# STM32.net
KiCad netlist of a schematic drawn in Altium Designer
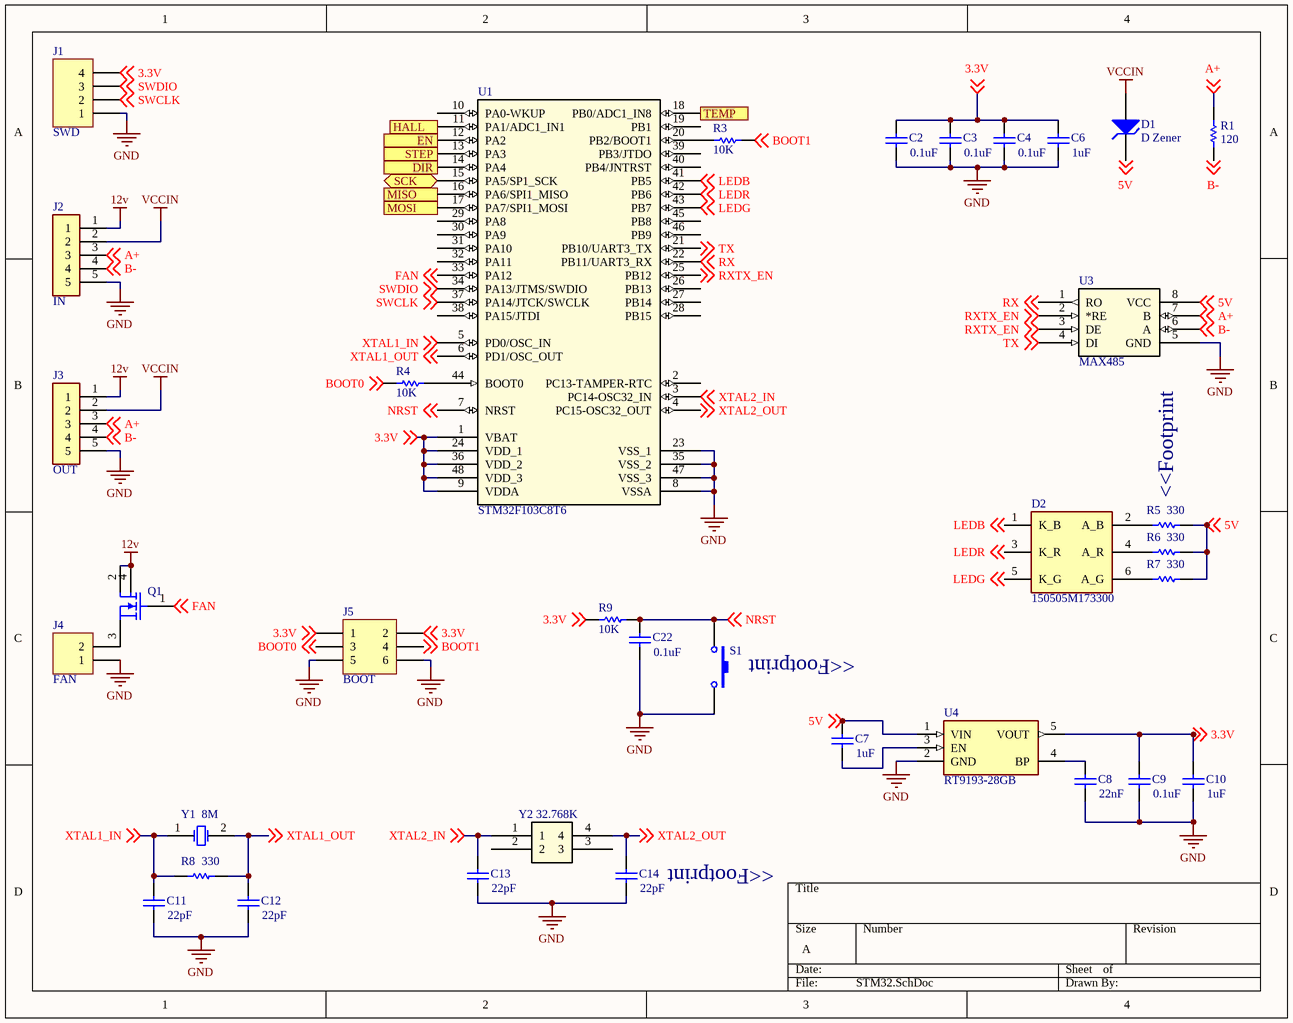
[diagram p0: STM32.SchDoc]

(export (version "E")
  (design (tool "Eeschema 10.0.6"))
  (components
    (comp (ref "C2")
      (value "0.1uF")
      (footprint "RAD-0.3")
      (description "Capacitor")
      (fields (field (name "PUBLISHER") "Altium Limited"))
      (libsource (lib "Miscellaneous Devices") (part "Cap"))
    )
    (comp (ref "C3")
      (value "0.1uF")
      (footprint "RAD-0.3")
      (description "Capacitor")
      (fields (field (name "PUBLISHER") "Altium Limited"))
      (libsource (lib "Miscellaneous Devices") (part "Cap"))
    )
    (comp (ref "C4")
      (value "0.1uF")
      (footprint "RAD-0.3")
      (description "Capacitor")
      (fields (field (name "PUBLISHER") "Altium Limited"))
      (libsource (lib "Miscellaneous Devices") (part "Cap"))
    )
    (comp (ref "C6")
      (value "1uF")
      (footprint "RAD-0.3")
      (description "Capacitor")
      (fields (field (name "PUBLISHER") "Altium Limited"))
      (libsource (lib "Miscellaneous Devices") (part "Cap"))
    )
    (comp (ref "C7")
      (value "1uF")
      (footprint "RAD-0.3")
      (description "Capacitor")
      (fields (field (name "PUBLISHER") "Altium Limited"))
      (libsource (lib "Miscellaneous Devices") (part "Cap"))
    )
    (comp (ref "C8")
      (value "22nF")
      (footprint "RAD-0.3")
      (description "Capacitor")
      (fields (field (name "PUBLISHER") "Altium Limited"))
      (libsource (lib "Miscellaneous Devices") (part "Cap"))
    )
    (comp (ref "C9")
      (value "0.1uF")
      (footprint "RAD-0.3")
      (description "Capacitor")
      (fields (field (name "PUBLISHER") "Altium Limited"))
      (libsource (lib "Miscellaneous Devices") (part "Cap"))
    )
    (comp (ref "C10")
      (value "1uF")
      (footprint "RAD-0.3")
      (description "Capacitor")
      (fields (field (name "PUBLISHER") "Altium Limited"))
      (libsource (lib "Miscellaneous Devices") (part "Cap"))
    )
    (comp (ref "C11")
      (value "22pF")
      (footprint "RAD-0.3")
      (description "Capacitor")
      (fields (field (name "PUBLISHER") "Altium Limited"))
      (libsource (lib "Miscellaneous Devices") (part "Cap"))
    )
    (comp (ref "C12")
      (value "22pF")
      (footprint "RAD-0.3")
      (description "Capacitor")
      (fields (field (name "PUBLISHER") "Altium Limited"))
      (libsource (lib "Miscellaneous Devices") (part "Cap"))
    )
    (comp (ref "C13")
      (value "22pF")
      (footprint "RAD-0.3")
      (description "Capacitor")
      (fields (field (name "PUBLISHER") "Altium Limited"))
      (libsource (lib "Miscellaneous Devices") (part "Cap"))
    )
    (comp (ref "C14")
      (value "22pF")
      (footprint "RAD-0.3")
      (description "Capacitor")
      (fields (field (name "PUBLISHER") "Altium Limited"))
      (libsource (lib "Miscellaneous Devices") (part "Cap"))
    )
    (comp (ref "C22")
      (value "0.1uF")
      (footprint "RAD-0.3")
      (description "Capacitor")
      (fields (field (name "PUBLISHER") "Altium Limited"))
      (libsource (lib "Miscellaneous Devices") (part "Cap"))
    )
    (comp (ref "D1")
      (value "D Zener")
      (footprint "DIODE-0.7")
      (description "Zener Diode")
      (fields (field (name "PUBLISHER") "Altium Limited"))
      (libsource (lib "Miscellaneous Devices") (part "D Zener"))
    )
    (comp (ref "D2")
      (value "150505M173300")
      (footprint "SamacSys:150505M173300")
      (description "LED")
      (fields
        (field (name "MOUSER PART NUMBER") "710-150505M173300")
        (field (name "RS PART NUMBER") "1766248P")
      )
      (libsource (lib "Schematic_Emile") (part "150505M173300"))
    )
    (comp (ref "J1")
      (value "SWD")
      (footprint "HDR1X4")
      (description "Header, 4-Pin")
      (fields (field (name "PUBLISHER") "Altium Limited"))
      (libsource (lib "Miscellaneous Connectors") (part "Header 4"))
    )
    (comp (ref "J2")
      (value "IN")
      (footprint "Footprint_Emile:S5BXHA1LFSN")
      (description "Connector")
      (fields (field (name "MANUFACTURER_PART_NUMBER") "S5B-XH-A-1(LF)(SN)"))
      (libsource (lib "Schematic_Emile") (part "JST 5POS"))
    )
    (comp (ref "J3")
      (value "OUT")
      (footprint "Footprint_Emile:S5BXHA1LFSN")
      (description "Connector")
      (fields (field (name "MANUFACTURER_PART_NUMBER") "S5B-XH-A-1(LF)(SN)"))
      (libsource (lib "Schematic_Emile") (part "JST 5POS"))
    )
    (comp (ref "J4")
      (value "FAN")
      (footprint "HDR1X2")
      (description "Header, 2-Pin")
      (fields (field (name "PUBLISHER") "Altium Limited"))
      (libsource (lib "Miscellaneous Connectors") (part "Header 2"))
    )
    (comp (ref "J5")
      (value "BOOT")
      (footprint "HDR2X3")
      (description "Header, 3-Pin, Dual row")
      (fields (field (name "PUBLISHER") "Altium Limited"))
      (libsource (lib "Miscellaneous Connectors") (part "Header 3X2"))
    )
    (comp (ref "Q1")
      (value "MOSFET N-CH")
      (footprint "SOT223_M")
      (description "55V 7A SOT223")
      (libsource (lib "Schematic_Emile") (part "MOSFET N-CH"))
    )
    (comp (ref "R1")
      (value "120")
      (footprint "AXIAL-0.3")
      (description "Resistor")
      (fields (field (name "PUBLISHER") "Altium Limited"))
      (libsource (lib "Miscellaneous Devices") (part "Res1"))
    )
    (comp (ref "R3")
      (value "10K")
      (footprint "AXIAL-0.3")
      (description "Resistor")
      (fields (field (name "PUBLISHER") "Altium Limited"))
      (libsource (lib "Miscellaneous Devices") (part "Res1"))
    )
    (comp (ref "R4")
      (value "10K")
      (footprint "AXIAL-0.3")
      (description "Resistor")
      (fields (field (name "PUBLISHER") "Altium Limited"))
      (libsource (lib "Miscellaneous Devices") (part "Res1"))
    )
    (comp (ref "R5")
      (value "330")
      (footprint "AXIAL-0.3")
      (description "Resistor")
      (fields (field (name "PUBLISHER") "Altium Limited"))
      (libsource (lib "Miscellaneous Devices") (part "Res1"))
    )
    (comp (ref "R6")
      (value "330")
      (footprint "AXIAL-0.3")
      (description "Resistor")
      (fields (field (name "PUBLISHER") "Altium Limited"))
      (libsource (lib "Miscellaneous Devices") (part "Res1"))
    )
    (comp (ref "R7")
      (value "330")
      (footprint "AXIAL-0.3")
      (description "Resistor")
      (fields (field (name "PUBLISHER") "Altium Limited"))
      (libsource (lib "Miscellaneous Devices") (part "Res1"))
    )
    (comp (ref "R8")
      (value "330")
      (footprint "AXIAL-0.3")
      (description "Resistor")
      (fields (field (name "PUBLISHER") "Altium Limited"))
      (libsource (lib "Miscellaneous Devices") (part "Res1"))
    )
    (comp (ref "R9")
      (value "10K")
      (footprint "AXIAL-0.3")
      (description "Resistor")
      (fields (field (name "PUBLISHER") "Altium Limited"))
      (libsource (lib "Miscellaneous Devices") (part "Res1"))
    )
    (comp (ref "S1")
      (value "SW-PB")
      (footprint "SPST-2")
      (description "Switch")
      (fields (field (name "PUBLISHER") "Altium Limited"))
      (libsource (lib "Miscellaneous Devices") (part "SW-PB"))
    )
    (comp (ref "U1")
      (value "STM32F103C8T6")
      (footprint "LQFP-48")
      (description "Integrated Circuit STM32")
      (fields (field (name "COPYRIGHT") "Copyright (C) 2018 Accelerated Designs. All rights reserved"))
      (libsource (lib "Schematic_Emile") (part "STM32F103C8T6"))
    )
    (comp (ref "U3")
      (value "MAX485")
      (footprint "21-0043D_8")
      (description "RS485 Communication")
      (fields
        (field (name "MANUFACTURER_PART_NUMBER") "MAX485CPA+")
        (field (name "COPYRIGHT") "Copyright (C) 2018 Accelerated Designs. All rights reserved")
      )
      (libsource (lib "Schematic_Emile") (part "MAX485CPA+"))
    )
    (comp (ref "U4")
      (value "RT9193-28GB")
      (footprint "SamacSys:SOT94P279X130-5N")
      (description "Voltage Regulator 3.3V")
      (libsource (lib "Schematic_Emile") (part "RT9193-28GB"))
    )
    (comp (ref "Y1")
      (value "8M")
      (footprint "ATS080B-E")
      (description "Crystal Oscillator")
      (fields (field (name "PUBLISHER") "Altium Limited"))
      (libsource (lib "Miscellaneous Devices") (part "XTAL"))
    )
    (comp (ref "Y2 32.768K")
      (value "~")
      (footprint "XTAL_0:ROHS")
      (description "Crystal / Oscillator 32.768KHz for low power consumption")
      (fields
        (field (name "MANUFACTURER_PART_NUMBER") "MC-306 32.7680K-E0:ROHS")
        (field (name "COPYRIGHT") "Copyright (C) 2018 Accelerated Designs. All rights reserved")
      )
      (libsource (lib "Schematic_Emile") (part "MC-306 32.7680K-"))
    )
  )
  (nets
    (net (code "1") (name "/DIR") (class "Default")
      (node (ref "U1") (pin "14") (pinfunction "PA4_14") (pintype "bidirectional"))
    )
    (net (code "2") (name "/EN") (class "Default")
      (node (ref "U1") (pin "12") (pinfunction "PA2_12") (pintype "bidirectional"))
    )
    (net (code "3") (name "/HALL") (class "Default")
      (node (ref "U1") (pin "11") (pinfunction "PA1/ADC1_IN1_11") (pintype "bidirectional"))
    )
    (net (code "4") (name "/MISO") (class "Default")
      (node (ref "U1") (pin "16") (pinfunction "PA6/SPI1_MISO_16") (pintype "bidirectional"))
    )
    (net (code "5") (name "/MOSI") (class "Default")
      (node (ref "U1") (pin "17") (pinfunction "PA7/SPI1_MOSI_17") (pintype "bidirectional"))
    )
    (net (code "6") (name "/SCK") (class "Default")
      (node (ref "U1") (pin "15") (pinfunction "PA5/SP1_SCK_15") (pintype "bidirectional"))
    )
    (net (code "7") (name "/STEP") (class "Default")
      (node (ref "U1") (pin "13") (pinfunction "PA3_13") (pintype "bidirectional"))
    )
    (net (code "8") (name "/TEMP") (class "Default")
      (node (ref "U1") (pin "18") (pinfunction "PB0/ADC1_IN8_18") (pintype "bidirectional"))
    )
    (net (code "9") (name "3.3V") (class "Default")
      (node (ref "C10") (pin "1") (pinfunction "1_1") (pintype "passive"))
      (node (ref "C2") (pin "1") (pinfunction "1_1") (pintype "passive"))
      (node (ref "C3") (pin "1") (pinfunction "1_1") (pintype "passive"))
      (node (ref "C4") (pin "1") (pinfunction "1_1") (pintype "passive"))
      (node (ref "C6") (pin "1") (pinfunction "1_1") (pintype "passive"))
      (node (ref "C9") (pin "1") (pinfunction "1_1") (pintype "passive"))
      (node (ref "J1") (pin "4") (pinfunction "4_4") (pintype "passive"))
      (node (ref "J5") (pin "1") (pinfunction "1_1") (pintype "passive"))
      (node (ref "J5") (pin "2") (pinfunction "2_2") (pintype "passive"))
      (node (ref "R9") (pin "1") (pinfunction "1_1") (pintype "passive"))
      (node (ref "U1") (pin "1") (pinfunction "VBAT_1") (pintype "power_in"))
      (node (ref "U1") (pin "24") (pinfunction "VDD_1_24") (pintype "power_in"))
      (node (ref "U1") (pin "36") (pinfunction "VDD_2_36") (pintype "power_in"))
      (node (ref "U1") (pin "48") (pinfunction "VDD_3_48") (pintype "power_in"))
      (node (ref "U1") (pin "9") (pinfunction "VDDA_9") (pintype "power_in"))
      (node (ref "U4") (pin "5") (pinfunction "VOUT_5") (pintype "output"))
    )
    (net (code "10") (name "5V") (class "Default")
      (node (ref "C7") (pin "1") (pinfunction "1_1") (pintype "passive"))
      (node (ref "D1") (pin "2") (pinfunction "K_2") (pintype "passive"))
      (node (ref "R5") (pin "1") (pinfunction "1_1") (pintype "passive"))
      (node (ref "R6") (pin "1") (pinfunction "1_1") (pintype "passive"))
      (node (ref "R7") (pin "1") (pinfunction "1_1") (pintype "passive"))
      (node (ref "U3") (pin "8") (pinfunction "VCC_8") (pintype "power_in"))
      (node (ref "U4") (pin "1") (pinfunction "VIN_1") (pintype "input"))
    )
    (net (code "11") (name "12v") (class "Default")
      (node (ref "J2") (pin "1") (pinfunction "1_1") (pintype "passive"))
      (node (ref "J3") (pin "1") (pinfunction "1_1") (pintype "passive"))
      (node (ref "Q1") (pin "2") (pinfunction "D_2") (pintype "passive"))
      (node (ref "Q1") (pin "4") (pinfunction "D_4") (pintype "passive"))
    )
    (net (code "12") (name "A+") (class "Default")
      (node (ref "J2") (pin "3") (pinfunction "3_3") (pintype "passive"))
      (node (ref "J3") (pin "3") (pinfunction "3_3") (pintype "passive"))
      (node (ref "R1") (pin "2") (pinfunction "2_2") (pintype "passive"))
      (node (ref "U3") (pin "7") (pinfunction "B_7") (pintype "bidirectional"))
    )
    (net (code "13") (name "B-") (class "Default")
      (node (ref "J2") (pin "4") (pinfunction "4_4") (pintype "passive"))
      (node (ref "J3") (pin "4") (pinfunction "4_4") (pintype "passive"))
      (node (ref "R1") (pin "1") (pinfunction "1_1") (pintype "passive"))
      (node (ref "U3") (pin "6") (pinfunction "A_6") (pintype "bidirectional"))
    )
    (net (code "14") (name "BOOT0") (class "Default")
      (node (ref "J5") (pin "3") (pinfunction "3_3") (pintype "passive"))
      (node (ref "R4") (pin "2") (pinfunction "2_2") (pintype "passive"))
    )
    (net (code "15") (name "BOOT1") (class "Default")
      (node (ref "J5") (pin "4") (pinfunction "4_4") (pintype "passive"))
      (node (ref "R3") (pin "1") (pinfunction "1_1") (pintype "passive"))
    )
    (net (code "16") (name "FAN") (class "Default")
      (node (ref "Q1") (pin "1") (pinfunction "G_1") (pintype "passive"))
      (node (ref "U1") (pin "33") (pinfunction "PA12_33") (pintype "bidirectional"))
    )
    (net (code "17") (name "GND") (class "Default")
      (node (ref "C10") (pin "2") (pinfunction "2_2") (pintype "passive"))
      (node (ref "C11") (pin "2") (pinfunction "2_2") (pintype "passive"))
      (node (ref "C12") (pin "2") (pinfunction "2_2") (pintype "passive"))
      (node (ref "C13") (pin "2") (pinfunction "2_2") (pintype "passive"))
      (node (ref "C14") (pin "2") (pinfunction "2_2") (pintype "passive"))
      (node (ref "C2") (pin "2") (pinfunction "2_2") (pintype "passive"))
      (node (ref "C22") (pin "2") (pinfunction "2_2") (pintype "passive"))
      (node (ref "C3") (pin "2") (pinfunction "2_2") (pintype "passive"))
      (node (ref "C4") (pin "2") (pinfunction "2_2") (pintype "passive"))
      (node (ref "C6") (pin "2") (pinfunction "2_2") (pintype "passive"))
      (node (ref "C8") (pin "2") (pinfunction "2_2") (pintype "passive"))
      (node (ref "C9") (pin "2") (pinfunction "2_2") (pintype "passive"))
      (node (ref "J1") (pin "1") (pinfunction "1_1") (pintype "passive"))
      (node (ref "J2") (pin "5") (pinfunction "5_5") (pintype "passive"))
      (node (ref "J3") (pin "5") (pinfunction "5_5") (pintype "passive"))
      (node (ref "J4") (pin "1") (pinfunction "1_1") (pintype "passive"))
      (node (ref "J5") (pin "5") (pinfunction "5_5") (pintype "passive"))
      (node (ref "J5") (pin "6") (pinfunction "6_6") (pintype "passive"))
      (node (ref "S1") (pin "2") (pinfunction "2_2") (pintype "passive"))
      (node (ref "U1") (pin "23") (pinfunction "VSS_1_23") (pintype "power_in"))
      (node (ref "U1") (pin "35") (pinfunction "VSS_2_35") (pintype "power_in"))
      (node (ref "U1") (pin "47") (pinfunction "VSS_3_47") (pintype "power_in"))
      (node (ref "U1") (pin "8") (pinfunction "VSSA_8") (pintype "power_in"))
      (node (ref "U3") (pin "5") (pinfunction "GND_5") (pintype "power_in"))
      (node (ref "U4") (pin "2") (pinfunction "GND_2") (pintype "power_in"))
    )
    (net (code "18") (name "LEDB") (class "Default")
      (node (ref "D2") (pin "1") (pinfunction "K_B_1") (pintype "passive"))
      (node (ref "U1") (pin "41") (pinfunction "PB5_41") (pintype "bidirectional"))
    )
    (net (code "19") (name "LEDG") (class "Default")
      (node (ref "D2") (pin "5") (pinfunction "K_G_5") (pintype "passive"))
      (node (ref "U1") (pin "43") (pinfunction "PB7_43") (pintype "bidirectional"))
    )
    (net (code "20") (name "LEDR") (class "Default")
      (node (ref "D2") (pin "3") (pinfunction "K_R_3") (pintype "passive"))
      (node (ref "U1") (pin "42") (pinfunction "PB6_42") (pintype "bidirectional"))
    )
    (net (code "21") (name "NRST") (class "Default")
      (node (ref "C22") (pin "1") (pinfunction "1_1") (pintype "passive"))
      (node (ref "R9") (pin "2") (pinfunction "2_2") (pintype "passive"))
      (node (ref "S1") (pin "1") (pinfunction "1_1") (pintype "passive"))
      (node (ref "U1") (pin "7") (pinfunction "NRST_7") (pintype "bidirectional"))
    )
    (net (code "22") (name "Net-(D2-A_B)") (class "Default")
      (node (ref "D2") (pin "2") (pinfunction "A_B_2") (pintype "passive"))
      (node (ref "R5") (pin "2") (pinfunction "2_2") (pintype "passive"))
    )
    (net (code "23") (name "Net-(D2-A_G)") (class "Default")
      (node (ref "D2") (pin "6") (pinfunction "A_G_6") (pintype "passive"))
      (node (ref "R7") (pin "2") (pinfunction "2_2") (pintype "passive"))
    )
    (net (code "24") (name "Net-(D2-A_R)") (class "Default")
      (node (ref "D2") (pin "4") (pinfunction "A_R_4") (pintype "passive"))
      (node (ref "R6") (pin "2") (pinfunction "2_2") (pintype "passive"))
    )
    (net (code "25") (name "Net-(Q1-S)") (class "Default")
      (node (ref "J4") (pin "2") (pinfunction "2_2") (pintype "passive"))
      (node (ref "Q1") (pin "3") (pinfunction "S_3") (pintype "passive"))
    )
    (net (code "26") (name "Net-(U1-BOOT0)") (class "Default")
      (node (ref "R4") (pin "1") (pinfunction "1_1") (pintype "passive"))
      (node (ref "U1") (pin "44") (pinfunction "BOOT0_44") (pintype "input"))
    )
    (net (code "27") (name "Net-(U1-PB2{slash}BOOT1)") (class "Default")
      (node (ref "R3") (pin "2") (pinfunction "2_2") (pintype "passive"))
      (node (ref "U1") (pin "20") (pinfunction "PB2/BOOT1_20") (pintype "bidirectional"))
    )
    (net (code "28") (name "Net-(U4-BP)") (class "Default")
      (node (ref "C8") (pin "1") (pinfunction "1_1") (pintype "passive"))
      (node (ref "U4") (pin "4") (pinfunction "BP_4") (pintype "passive"))
    )
    (net (code "29") (name "Net-(U4-EN)") (class "Default")
      (node (ref "C7") (pin "2") (pinfunction "2_2") (pintype "passive"))
      (node (ref "U4") (pin "3") (pinfunction "EN_3") (pintype "input"))
    )
    (net (code "30") (name "RX") (class "Default")
      (node (ref "U1") (pin "22") (pinfunction "PB11/UART3_RX_22") (pintype "bidirectional"))
      (node (ref "U3") (pin "1") (pinfunction "RO_1") (pintype "output"))
    )
    (net (code "31") (name "RXTX_EN") (class "Default")
      (node (ref "U1") (pin "25") (pinfunction "PB12_25") (pintype "bidirectional"))
      (node (ref "U3") (pin "2") (pinfunction "*RE_2") (pintype "input"))
      (node (ref "U3") (pin "3") (pinfunction "DE_3") (pintype "input"))
    )
    (net (code "32") (name "SWCLK") (class "Default")
      (node (ref "J1") (pin "2") (pinfunction "2_2") (pintype "passive"))
      (node (ref "U1") (pin "37") (pinfunction "PA14/JTCK/SWCLK_37") (pintype "bidirectional"))
    )
    (net (code "33") (name "SWDIO") (class "Default")
      (node (ref "J1") (pin "3") (pinfunction "3_3") (pintype "passive"))
      (node (ref "U1") (pin "34") (pinfunction "PA13/JTMS/SWDIO_34") (pintype "bidirectional"))
    )
    (net (code "34") (name "TX") (class "Default")
      (node (ref "U1") (pin "21") (pinfunction "PB10/UART3_TX_21") (pintype "bidirectional"))
      (node (ref "U3") (pin "4") (pinfunction "DI_4") (pintype "input"))
    )
    (net (code "35") (name "VCCIN") (class "Default")
      (node (ref "D1") (pin "1") (pinfunction "A_1") (pintype "passive"))
      (node (ref "J2") (pin "2") (pinfunction "2_2") (pintype "passive"))
      (node (ref "J3") (pin "2") (pinfunction "2_2") (pintype "passive"))
    )
    (net (code "36") (name "XTAL1_IN") (class "Default")
      (node (ref "C11") (pin "1") (pinfunction "1_1") (pintype "passive"))
      (node (ref "R8") (pin "2") (pinfunction "2_2") (pintype "passive"))
      (node (ref "U1") (pin "5") (pinfunction "PD0/OSC_IN_5") (pintype "bidirectional"))
      (node (ref "Y1") (pin "1") (pinfunction "OSC1_1") (pintype "passive"))
    )
    (net (code "37") (name "XTAL1_OUT") (class "Default")
      (node (ref "C12") (pin "1") (pinfunction "1_1") (pintype "passive"))
      (node (ref "R8") (pin "1") (pinfunction "1_1") (pintype "passive"))
      (node (ref "U1") (pin "6") (pinfunction "PD1/OSC_OUT_6") (pintype "bidirectional"))
      (node (ref "Y1") (pin "2") (pinfunction "OSC2_2") (pintype "passive"))
    )
    (net (code "38") (name "XTAL2_IN") (class "Default")
      (node (ref "C13") (pin "1") (pinfunction "1_1") (pintype "passive"))
      (node (ref "U1") (pin "3") (pinfunction "PC14-OSC32_IN_3") (pintype "bidirectional"))
      (node (ref "Y2 32.768K") (pin "1") (pinfunction "1_1") (pintype "passive"))
    )
    (net (code "39") (name "XTAL2_OUT") (class "Default")
      (node (ref "C14") (pin "1") (pinfunction "1_1") (pintype "passive"))
      (node (ref "U1") (pin "4") (pinfunction "PC15-OSC32_OUT_4") (pintype "bidirectional"))
      (node (ref "Y2 32.768K") (pin "4") (pinfunction "4_4") (pintype "passive"))
    )
    (net (code "40") (name "unconnected-(U1-PA0-WKUP-Pad10)") (class "Default")
      (node (ref "U1") (pin "10") (pinfunction "PA0-WKUP_10") (pintype "bidirectional"))
    )
    (net (code "41") (name "unconnected-(U1-PA8-Pad29)") (class "Default")
      (node (ref "U1") (pin "29") (pinfunction "PA8_29") (pintype "bidirectional"))
    )
    (net (code "42") (name "unconnected-(U1-PA9-Pad30)") (class "Default")
      (node (ref "U1") (pin "30") (pinfunction "PA9_30") (pintype "bidirectional"))
    )
    (net (code "43") (name "unconnected-(U1-PA10-Pad31)") (class "Default")
      (node (ref "U1") (pin "31") (pinfunction "PA10_31") (pintype "bidirectional"))
    )
    (net (code "44") (name "unconnected-(U1-PA11-Pad32)") (class "Default")
      (node (ref "U1") (pin "32") (pinfunction "PA11_32") (pintype "bidirectional"))
    )
    (net (code "45") (name "unconnected-(U1-PA15{slash}JTDI-Pad38)") (class "Default")
      (node (ref "U1") (pin "38") (pinfunction "PA15/JTDI_38") (pintype "bidirectional"))
    )
    (net (code "46") (name "unconnected-(U1-PB1-Pad19)") (class "Default")
      (node (ref "U1") (pin "19") (pinfunction "PB1_19") (pintype "bidirectional"))
    )
    (net (code "47") (name "unconnected-(U1-PB3{slash}JTDO-Pad39)") (class "Default")
      (node (ref "U1") (pin "39") (pinfunction "PB3/JTDO_39") (pintype "bidirectional"))
    )
    (net (code "48") (name "unconnected-(U1-PB4{slash}JNTRST-Pad40)") (class "Default")
      (node (ref "U1") (pin "40") (pinfunction "PB4/JNTRST_40") (pintype "bidirectional"))
    )
    (net (code "49") (name "unconnected-(U1-PB8-Pad45)") (class "Default")
      (node (ref "U1") (pin "45") (pinfunction "PB8_45") (pintype "bidirectional"))
    )
    (net (code "50") (name "unconnected-(U1-PB9-Pad46)") (class "Default")
      (node (ref "U1") (pin "46") (pinfunction "PB9_46") (pintype "bidirectional"))
    )
    (net (code "51") (name "unconnected-(U1-PB13-Pad26)") (class "Default")
      (node (ref "U1") (pin "26") (pinfunction "PB13_26") (pintype "bidirectional"))
    )
    (net (code "52") (name "unconnected-(U1-PB14-Pad27)") (class "Default")
      (node (ref "U1") (pin "27") (pinfunction "PB14_27") (pintype "bidirectional"))
    )
    (net (code "53") (name "unconnected-(U1-PB15-Pad28)") (class "Default")
      (node (ref "U1") (pin "28") (pinfunction "PB15_28") (pintype "bidirectional"))
    )
    (net (code "54") (name "unconnected-(U1-PC13-TAMPER-RTC-Pad2)") (class "Default")
      (node (ref "U1") (pin "2") (pinfunction "PC13-TAMPER-RTC_2") (pintype "bidirectional"))
    )
    (net (code "55") (name "unconnected-(Y2 32.768K-Pad2)") (class "Default")
      (node (ref "Y2 32.768K") (pin "2") (pinfunction "2_2") (pintype "passive"))
    )
    (net (code "56") (name "unconnected-(Y2 32.768K-Pad3)") (class "Default")
      (node (ref "Y2 32.768K") (pin "3") (pinfunction "3_3") (pintype "passive"))
    )
  )
)
